# 4_Connectors.net
KiCad netlist of a schematic drawn in Altium Designer
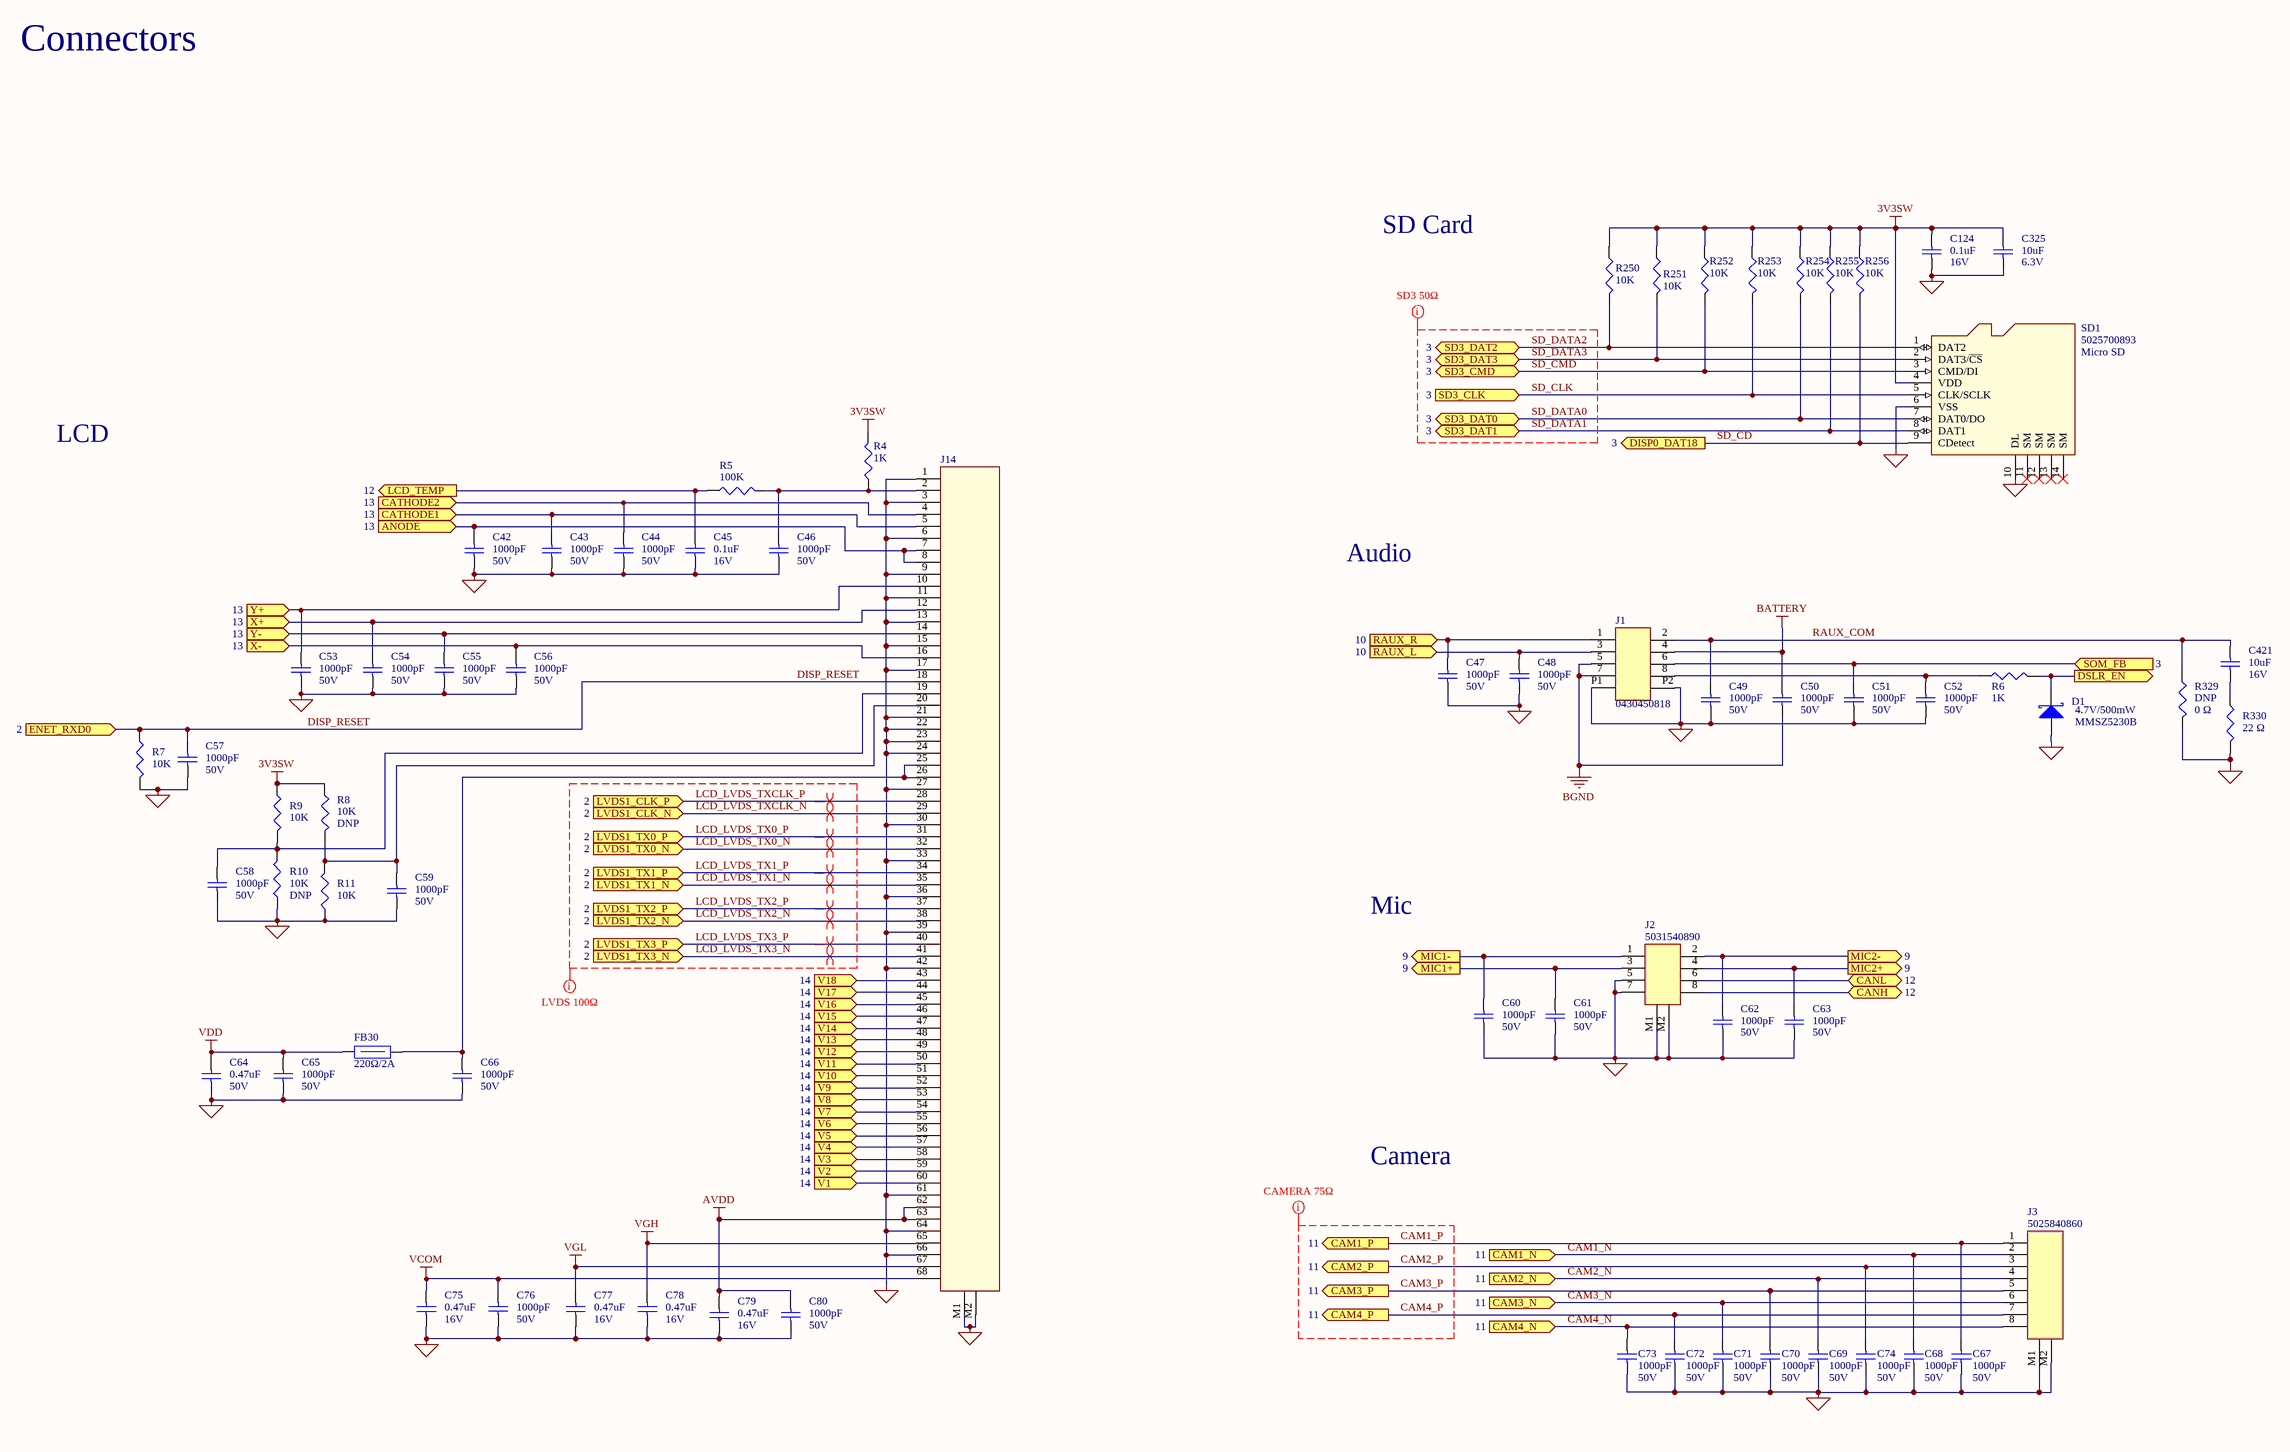
[diagram p0: 4 Connectors.SchDoc]

(export (version "E")
  (design (tool "Eeschema 10.0.6"))
  (components
    (comp (ref "C42")
      (value "1000pF")
      (footprint "CAP_0402")
      (description "Cap, Cer, 1000pF, 50V, 20%, X7R, 0402")
      (fields
        (field (name "TOLERANCE") "20%")
        (field (name "MANUFACTURER") "Murata Electronics North America")
        (field (name "VOLTAGE") "50V")
      )
      (libsource (lib "Firstview") (part "Cap 1000pF 50V 0402"))
    )
    (comp (ref "C43")
      (value "1000pF")
      (footprint "CAP_0402")
      (description "Cap, Cer, 1000pF, 50V, 20%, X7R, 0402")
      (fields
        (field (name "TOLERANCE") "20%")
        (field (name "MANUFACTURER") "Murata Electronics North America")
        (field (name "VOLTAGE") "50V")
      )
      (libsource (lib "Firstview") (part "Cap 1000pF 50V 0402"))
    )
    (comp (ref "C44")
      (value "1000pF")
      (footprint "CAP_0402")
      (description "Cap, Cer, 1000pF, 50V, 20%, X7R, 0402")
      (fields
        (field (name "TOLERANCE") "20%")
        (field (name "MANUFACTURER") "Murata Electronics North America")
        (field (name "VOLTAGE") "50V")
      )
      (libsource (lib "Firstview") (part "Cap 1000pF 50V 0402"))
    )
    (comp (ref "C45")
      (value "0.1uF")
      (footprint "CAP_0402")
      (description "Cap, Cer, 0.1uF, 16V, 10%, X7R, 0402")
      (fields
        (field (name "TOLERANCE") "±10%")
        (field (name "MANUFACTURER") "Murata Electronics North America")
        (field (name "VOLTAGE") "16V")
      )
      (libsource (lib "Firstview") (part "Cap 0.1uF 16V 0402"))
    )
    (comp (ref "C46")
      (value "1000pF")
      (footprint "CAP_0402")
      (description "Cap, Cer, 1000pF, 50V, 20%, X7R, 0402")
      (fields
        (field (name "TOLERANCE") "20%")
        (field (name "MANUFACTURER") "Murata Electronics North America")
        (field (name "VOLTAGE") "50V")
      )
      (libsource (lib "Firstview") (part "Cap 1000pF 50V 0402"))
    )
    (comp (ref "C47")
      (value "1000pF")
      (footprint "CAP_0402")
      (description "Cap, Cer, 1000pF, 50V, 20%, X7R, 0402")
      (fields
        (field (name "TOLERANCE") "20%")
        (field (name "MANUFACTURER") "Murata Electronics North America")
        (field (name "VOLTAGE") "50V")
      )
      (libsource (lib "Firstview") (part "Cap 1000pF 50V 0402"))
    )
    (comp (ref "C48")
      (value "1000pF")
      (footprint "CAP_0402")
      (description "Cap, Cer, 1000pF, 50V, 20%, X7R, 0402")
      (fields
        (field (name "TOLERANCE") "20%")
        (field (name "MANUFACTURER") "Murata Electronics North America")
        (field (name "VOLTAGE") "50V")
      )
      (libsource (lib "Firstview") (part "Cap 1000pF 50V 0402"))
    )
    (comp (ref "C49")
      (value "1000pF")
      (footprint "CAP_0402")
      (description "Cap, Cer, 1000pF, 50V, 20%, X7R, 0402")
      (fields
        (field (name "TOLERANCE") "20%")
        (field (name "MANUFACTURER") "Murata Electronics North America")
        (field (name "VOLTAGE") "50V")
      )
      (libsource (lib "Firstview") (part "Cap 1000pF 50V 0402"))
    )
    (comp (ref "C50")
      (value "1000pF")
      (footprint "CAP_0402")
      (description "Cap, Cer, 1000pF, 50V, 20%, X7R, 0402")
      (fields
        (field (name "TOLERANCE") "20%")
        (field (name "MANUFACTURER") "Murata Electronics North America")
        (field (name "VOLTAGE") "50V")
      )
      (libsource (lib "Firstview") (part "Cap 1000pF 50V 0402"))
    )
    (comp (ref "C51")
      (value "1000pF")
      (footprint "CAP_0402")
      (description "Cap, Cer, 1000pF, 50V, 20%, X7R, 0402")
      (fields
        (field (name "TOLERANCE") "20%")
        (field (name "MANUFACTURER") "Murata Electronics North America")
        (field (name "VOLTAGE") "50V")
      )
      (libsource (lib "Firstview") (part "Cap 1000pF 50V 0402"))
    )
    (comp (ref "C52")
      (value "1000pF")
      (footprint "CAP_0402")
      (description "Cap, Cer, 1000pF, 50V, 20%, X7R, 0402")
      (fields
        (field (name "TOLERANCE") "20%")
        (field (name "MANUFACTURER") "Murata Electronics North America")
        (field (name "VOLTAGE") "50V")
      )
      (libsource (lib "Firstview") (part "Cap 1000pF 50V 0402"))
    )
    (comp (ref "C53")
      (value "1000pF")
      (footprint "CAP_0402")
      (description "Cap, Cer, 1000pF, 50V, 20%, X7R, 0402")
      (fields
        (field (name "TOLERANCE") "20%")
        (field (name "MANUFACTURER") "Murata Electronics North America")
        (field (name "VOLTAGE") "50V")
      )
      (libsource (lib "Firstview") (part "Cap 1000pF 50V 0402"))
    )
    (comp (ref "C54")
      (value "1000pF")
      (footprint "CAP_0402")
      (description "Cap, Cer, 1000pF, 50V, 20%, X7R, 0402")
      (fields
        (field (name "TOLERANCE") "20%")
        (field (name "MANUFACTURER") "Murata Electronics North America")
        (field (name "VOLTAGE") "50V")
      )
      (libsource (lib "Firstview") (part "Cap 1000pF 50V 0402"))
    )
    (comp (ref "C55")
      (value "1000pF")
      (footprint "CAP_0402")
      (description "Cap, Cer, 1000pF, 50V, 20%, X7R, 0402")
      (fields
        (field (name "TOLERANCE") "20%")
        (field (name "MANUFACTURER") "Murata Electronics North America")
        (field (name "VOLTAGE") "50V")
      )
      (libsource (lib "Firstview") (part "Cap 1000pF 50V 0402"))
    )
    (comp (ref "C56")
      (value "1000pF")
      (footprint "CAP_0402")
      (description "Cap, Cer, 1000pF, 50V, 20%, X7R, 0402")
      (fields
        (field (name "TOLERANCE") "20%")
        (field (name "MANUFACTURER") "Murata Electronics North America")
        (field (name "VOLTAGE") "50V")
      )
      (libsource (lib "Firstview") (part "Cap 1000pF 50V 0402"))
    )
    (comp (ref "C57")
      (value "1000pF")
      (footprint "CAP_0402")
      (description "Cap, Cer, 1000pF, 50V, 20%, X7R, 0402")
      (fields
        (field (name "TOLERANCE") "20%")
        (field (name "MANUFACTURER") "Murata Electronics North America")
        (field (name "VOLTAGE") "50V")
      )
      (libsource (lib "Firstview") (part "Cap 1000pF 50V 0402"))
    )
    (comp (ref "C58")
      (value "1000pF")
      (footprint "CAP_0402")
      (description "Cap, Cer, 1000pF, 50V, 20%, X7R, 0402")
      (fields
        (field (name "TOLERANCE") "20%")
        (field (name "MANUFACTURER") "Murata Electronics North America")
        (field (name "VOLTAGE") "50V")
      )
      (libsource (lib "Firstview") (part "Cap 1000pF 50V 0402"))
    )
    (comp (ref "C59")
      (value "1000pF")
      (footprint "CAP_0402")
      (description "Cap, Cer, 1000pF, 50V, 20%, X7R, 0402")
      (fields
        (field (name "TOLERANCE") "20%")
        (field (name "MANUFACTURER") "Murata Electronics North America")
        (field (name "VOLTAGE") "50V")
      )
      (libsource (lib "Firstview") (part "Cap 1000pF 50V 0402"))
    )
    (comp (ref "C60")
      (value "1000pF")
      (footprint "CAP_0402")
      (description "Cap, Cer, 1000pF, 50V, 20%, X7R, 0402")
      (fields
        (field (name "TOLERANCE") "20%")
        (field (name "MANUFACTURER") "Murata Electronics North America")
        (field (name "VOLTAGE") "50V")
      )
      (libsource (lib "Firstview") (part "Cap 1000pF 50V 0402"))
    )
    (comp (ref "C61")
      (value "1000pF")
      (footprint "CAP_0402")
      (description "Cap, Cer, 1000pF, 50V, 20%, X7R, 0402")
      (fields
        (field (name "TOLERANCE") "20%")
        (field (name "MANUFACTURER") "Murata Electronics North America")
        (field (name "VOLTAGE") "50V")
      )
      (libsource (lib "Firstview") (part "Cap 1000pF 50V 0402"))
    )
    (comp (ref "C62")
      (value "1000pF")
      (footprint "CAP_0402")
      (description "Cap, Cer, 1000pF, 50V, 20%, X7R, 0402")
      (fields
        (field (name "TOLERANCE") "20%")
        (field (name "MANUFACTURER") "Murata Electronics North America")
        (field (name "VOLTAGE") "50V")
      )
      (libsource (lib "Firstview") (part "Cap 1000pF 50V 0402"))
    )
    (comp (ref "C63")
      (value "1000pF")
      (footprint "CAP_0402")
      (description "Cap, Cer, 1000pF, 50V, 20%, X7R, 0402")
      (fields
        (field (name "TOLERANCE") "20%")
        (field (name "MANUFACTURER") "Murata Electronics North America")
        (field (name "VOLTAGE") "50V")
      )
      (libsource (lib "Firstview") (part "Cap 1000pF 50V 0402"))
    )
    (comp (ref "C64")
      (value "0.47uF")
      (footprint "CAP_1206")
      (description "Cap, Cer, 0.47uF, 50V, 10%, X7R, 1206")
      (fields
        (field (name "MANUFACTURER") "Yageo")
        (field (name "TOLERANCE") "10%")
        (field (name "VOLTAGE") "50V")
      )
      (libsource (lib "Firstview") (part "Cap 0.47uF 50V 1206"))
    )
    (comp (ref "C65")
      (value "1000pF")
      (footprint "CAP_0402")
      (description "Cap, Cer, 1000pF, 50V, 20%, X7R, 0402")
      (fields
        (field (name "TOLERANCE") "20%")
        (field (name "MANUFACTURER") "Murata Electronics North America")
        (field (name "VOLTAGE") "50V")
      )
      (libsource (lib "Firstview") (part "Cap 1000pF 50V 0402"))
    )
    (comp (ref "C66")
      (value "1000pF")
      (footprint "CAP_0402")
      (description "Cap, Cer, 1000pF, 50V, 20%, X7R, 0402")
      (fields
        (field (name "TOLERANCE") "20%")
        (field (name "MANUFACTURER") "Murata Electronics North America")
        (field (name "VOLTAGE") "50V")
      )
      (libsource (lib "Firstview") (part "Cap 1000pF 50V 0402"))
    )
    (comp (ref "C67")
      (value "1000pF")
      (footprint "CAP_0402")
      (description "Cap, Cer, 1000pF, 50V, 20%, X7R, 0402")
      (fields
        (field (name "TOLERANCE") "20%")
        (field (name "MANUFACTURER") "Murata Electronics North America")
        (field (name "VOLTAGE") "50V")
      )
      (libsource (lib "Firstview") (part "Cap 1000pF 50V 0402"))
    )
    (comp (ref "C68")
      (value "1000pF")
      (footprint "CAP_0402")
      (description "Cap, Cer, 1000pF, 50V, 20%, X7R, 0402")
      (fields
        (field (name "TOLERANCE") "20%")
        (field (name "MANUFACTURER") "Murata Electronics North America")
        (field (name "VOLTAGE") "50V")
      )
      (libsource (lib "Firstview") (part "Cap 1000pF 50V 0402"))
    )
    (comp (ref "C69")
      (value "1000pF")
      (footprint "CAP_0402")
      (description "Cap, Cer, 1000pF, 50V, 20%, X7R, 0402")
      (fields
        (field (name "TOLERANCE") "20%")
        (field (name "MANUFACTURER") "Murata Electronics North America")
        (field (name "VOLTAGE") "50V")
      )
      (libsource (lib "Firstview") (part "Cap 1000pF 50V 0402"))
    )
    (comp (ref "C70")
      (value "1000pF")
      (footprint "CAP_0402")
      (description "Cap, Cer, 1000pF, 50V, 20%, X7R, 0402")
      (fields
        (field (name "TOLERANCE") "20%")
        (field (name "MANUFACTURER") "Murata Electronics North America")
        (field (name "VOLTAGE") "50V")
      )
      (libsource (lib "Firstview") (part "Cap 1000pF 50V 0402"))
    )
    (comp (ref "C71")
      (value "1000pF")
      (footprint "CAP_0402")
      (description "Cap, Cer, 1000pF, 50V, 20%, X7R, 0402")
      (fields
        (field (name "TOLERANCE") "20%")
        (field (name "MANUFACTURER") "Murata Electronics North America")
        (field (name "VOLTAGE") "50V")
      )
      (libsource (lib "Firstview") (part "Cap 1000pF 50V 0402"))
    )
    (comp (ref "C72")
      (value "1000pF")
      (footprint "CAP_0402")
      (description "Cap, Cer, 1000pF, 50V, 20%, X7R, 0402")
      (fields
        (field (name "TOLERANCE") "20%")
        (field (name "MANUFACTURER") "Murata Electronics North America")
        (field (name "VOLTAGE") "50V")
      )
      (libsource (lib "Firstview") (part "Cap 1000pF 50V 0402"))
    )
    (comp (ref "C73")
      (value "1000pF")
      (footprint "CAP_0402")
      (description "Cap, Cer, 1000pF, 50V, 20%, X7R, 0402")
      (fields
        (field (name "TOLERANCE") "20%")
        (field (name "MANUFACTURER") "Murata Electronics North America")
        (field (name "VOLTAGE") "50V")
      )
      (libsource (lib "Firstview") (part "Cap 1000pF 50V 0402"))
    )
    (comp (ref "C74")
      (value "1000pF")
      (footprint "CAP_0402")
      (description "Cap, Cer, 1000pF, 50V, 20%, X7R, 0402")
      (fields
        (field (name "TOLERANCE") "20%")
        (field (name "MANUFACTURER") "Murata Electronics North America")
        (field (name "VOLTAGE") "50V")
      )
      (libsource (lib "Firstview") (part "Cap 1000pF 50V 0402"))
    )
    (comp (ref "C75")
      (value "0.47uF")
      (footprint "CAP_0603")
      (description "Cap, Cer, 0.47uF, 16V, 10%, X8R, 0603")
      (fields
        (field (name "MANUFACTURER") "TDK Corporation")
        (field (name "TOLERANCE") "10%")
        (field (name "VOLTAGE") "16V")
      )
      (libsource (lib "Firstview") (part "Cap 0.47uF 16V 0603"))
    )
    (comp (ref "C76")
      (value "1000pF")
      (footprint "CAP_0402")
      (description "Cap, Cer, 1000pF, 50V, 20%, X7R, 0402")
      (fields
        (field (name "TOLERANCE") "20%")
        (field (name "MANUFACTURER") "Murata Electronics North America")
        (field (name "VOLTAGE") "50V")
      )
      (libsource (lib "Firstview") (part "Cap 1000pF 50V 0402"))
    )
    (comp (ref "C77")
      (value "0.47uF")
      (footprint "CAP_0603")
      (description "Cap, Cer, 0.47uF, 16V, 10%, X8R, 0603")
      (fields
        (field (name "MANUFACTURER") "TDK Corporation")
        (field (name "TOLERANCE") "10%")
        (field (name "VOLTAGE") "16V")
      )
      (libsource (lib "Firstview") (part "Cap 0.47uF 16V 0603"))
    )
    (comp (ref "C78")
      (value "0.47uF")
      (footprint "CAP_0603")
      (description "Cap, Cer, 0.47uF, 16V, 10%, X8R, 0603")
      (fields
        (field (name "MANUFACTURER") "TDK Corporation")
        (field (name "TOLERANCE") "10%")
        (field (name "VOLTAGE") "16V")
      )
      (libsource (lib "Firstview") (part "Cap 0.47uF 16V 0603"))
    )
    (comp (ref "C79")
      (value "0.47uF")
      (footprint "CAP_0603")
      (description "Cap, Cer, 0.47uF, 16V, 10%, X8R, 0603")
      (fields
        (field (name "MANUFACTURER") "TDK Corporation")
        (field (name "TOLERANCE") "10%")
        (field (name "VOLTAGE") "16V")
      )
      (libsource (lib "Firstview") (part "Cap 0.47uF 16V 0603"))
    )
    (comp (ref "C80")
      (value "1000pF")
      (footprint "CAP_0402")
      (description "Cap, Cer, 1000pF, 50V, 20%, X7R, 0402")
      (fields
        (field (name "TOLERANCE") "20%")
        (field (name "MANUFACTURER") "Murata Electronics North America")
        (field (name "VOLTAGE") "50V")
      )
      (libsource (lib "Firstview") (part "Cap 1000pF 50V 0402"))
    )
    (comp (ref "C124")
      (value "0.1uF")
      (footprint "CAP_0402")
      (description "Cap, Cer, 0.1uF, 16V, 10%, X7R, 0402")
      (fields
        (field (name "TOLERANCE") "±10%")
        (field (name "MANUFACTURER") "Murata Electronics North America")
        (field (name "VOLTAGE") "16V")
      )
      (libsource (lib "Firstview") (part "Cap 0.1uF 16V 0402"))
    )
    (comp (ref "C325")
      (value "10uF")
      (footprint "CAP_0402")
      (description "Cap, Cer, 10uF, 6.3V, 20%, X5R, 0402")
      (fields
        (field (name "TOLERANCE") "±20%")
        (field (name "MANUFACTURER") "Samsung Electro-Mechanics America, Inc")
        (field (name "VOLTAGE") "6.3V")
      )
      (libsource (lib "Firstview") (part "Cap 10uF 6.3V 0402"))
    )
    (comp (ref "C421")
      (value "10uF")
      (footprint "CAP_0603")
      (description "Cap, Cer, 10uF, 16V, 20%, X5R, 0603")
      (fields
        (field (name "TOLERANCE") "±20%")
        (field (name "MANUFACTURER") "Murata Electronics North America")
        (field (name "VOLTAGE") "16V")
      )
      (libsource (lib "Firstview") (part "Cap 10uF 16V 0603"))
    )
    (comp (ref "D1")
      (value "MMSZ5230B")
      (footprint "SOD-123_MMSZ5230B")
      (description "Diode, Zener, 4.7V, 500mW, SOD-123")
      (fields (field (name "MANUFACTURER") "Diodes Incorporated") (field (name "ALTIUM_VALUE") "4.7V/500mW"))
      (libsource (lib "Firstview") (part "MMSZ5230B"))
    )
    (comp (ref "FB30")
      (value "220Ω/2A")
      (footprint "IND_0805")
      (description "Ind, Ferrite Bead, 220R, 50mOhm, 2A, 0805")
      (fields (field (name "MANUFACTURER") "Taiyo Yuden") (field (name "Comment") "BKP2125HS221-T"))
      (libsource (lib "Firstview") (part "BKP2125HS221-T"))
    )
    (comp (ref "J1")
      (value "0430450818")
      (footprint "CON_0430450818")
      (description "Conn, Header, 8 pos, 3mm pitch, SMD")
      (fields (field (name "MANUFACTURER") "Molex Inc"))
      (libsource (lib "Firstview") (part "0430450818"))
    )
    (comp (ref "J2")
      (value "5031540890")
      (footprint "CON_5031540890")
      (description "Conn, Receptacle, 8 pos, 1.5mm pitch, SMD")
      (fields (field (name "MANUFACTURER") "Molex Inc"))
      (libsource (lib "Firstview") (part "5031540890"))
    )
    (comp (ref "J3")
      (value "5025840860")
      (footprint "CON_5025840860")
      (description "Conn, Receptacle, 8 pos, 1.5mm pitch, SMD")
      (fields (field (name "MANUFACTURER") "Molex Inc"))
      (libsource (lib "Firstview") (part "5025840860"))
    )
    (comp (ref "J14")
      (value "FH28E-68S-0.5SH(05)")
      (footprint "CON_FH28E-68S-0.5SH(05)")
      (description "Conn, FPC/FFC, 68Pos, .5MM, Horz., SMD")
      (fields (field (name "MANUFACTURER") "Hirose Electric Co Ltd"))
      (libsource (lib "Firstview") (part "FH28E-68S-0.5SH(05)"))
    )
    (comp (ref "R4")
      (value "1K")
      (footprint "RES_0402")
      (description "Res, 1K, 0.063W, 1%, 0402")
      (fields (field (name "TOLERANCE") "±1%") (field (name "MANUFACTURER") "Vishay Dale"))
      (libsource (lib "Firstview") (part "Res 1K 0.063W"))
    )
    (comp (ref "R5")
      (value "100K")
      (footprint "RES_0402")
      (description "Res, 100K, 0.1W, 1%, 0402")
      (fields
        (field (name "MANUFACTURER") "Panasonic Electronic Components")
        (field (name "Comment") "Res 100K 0.1W")
      )
      (libsource (lib "Firstview") (part "Res 100K 0.1W"))
    )
    (comp (ref "R6")
      (value "1K")
      (footprint "RES_0402")
      (description "Res, 1K, 0.063W, 1%, 0402")
      (fields (field (name "TOLERANCE") "±1%") (field (name "MANUFACTURER") "Vishay Dale"))
      (libsource (lib "Firstview") (part "Res 1K 0.063W"))
    )
    (comp (ref "R7")
      (value "10K")
      (footprint "RES_0402")
      (description "Res, 10K, 1/16W, 1%, 0402")
      (fields (field (name "MANUFACTURER") "Yageo") (field (name "Comment") "Res 10K 0.063W"))
      (libsource (lib "Firstview") (part "Res 10K 0.063W"))
    )
    (comp (ref "R8")
      (value "10K")
      (footprint "RES_0402")
      (description "Res, 10K, 1/16W, 1%, 0402")
      (fields
        (field (name "DNP") "DNP")
        (field (name "MANUFACTURER") "Yageo")
        (field (name "Comment") "Res 10K 0.063W")
      )
      (libsource (lib "Firstview") (part "Res 10K 0.063W"))
    )
    (comp (ref "R9")
      (value "10K")
      (footprint "RES_0402")
      (description "Res, 10K, 1/16W, 1%, 0402")
      (fields (field (name "MANUFACTURER") "Yageo") (field (name "Comment") "Res 10K 0.063W"))
      (libsource (lib "Firstview") (part "Res 10K 0.063W"))
    )
    (comp (ref "R10")
      (value "10K")
      (footprint "RES_0402")
      (description "Res, 10K, 1/16W, 1%, 0402")
      (fields
        (field (name "DNP") "DNP")
        (field (name "MANUFACTURER") "Yageo")
        (field (name "Comment") "Res 10K 0.063W")
      )
      (libsource (lib "Firstview") (part "Res 10K 0.063W"))
    )
    (comp (ref "R11")
      (value "10K")
      (footprint "RES_0402")
      (description "Res, 10K, 1/16W, 1%, 0402")
      (fields (field (name "MANUFACTURER") "Yageo") (field (name "Comment") "Res 10K 0.063W"))
      (libsource (lib "Firstview") (part "Res 10K 0.063W"))
    )
    (comp (ref "R250")
      (value "10K")
      (footprint "RES_0402")
      (description "Res, 10K, 1/16W, 1%, 0402")
      (fields (field (name "MANUFACTURER") "Yageo") (field (name "Comment") "Res 10K 0.063W"))
      (libsource (lib "Firstview") (part "Res 10K 0.063W"))
    )
    (comp (ref "R251")
      (value "10K")
      (footprint "RES_0402")
      (description "Res, 10K, 1/16W, 1%, 0402")
      (fields (field (name "MANUFACTURER") "Yageo") (field (name "Comment") "Res 10K 0.063W"))
      (libsource (lib "Firstview") (part "Res 10K 0.063W"))
    )
    (comp (ref "R252")
      (value "10K")
      (footprint "RES_0402")
      (description "Res, 10K, 1/16W, 1%, 0402")
      (fields (field (name "MANUFACTURER") "Yageo") (field (name "Comment") "Res 10K 0.063W"))
      (libsource (lib "Firstview") (part "Res 10K 0.063W"))
    )
    (comp (ref "R253")
      (value "10K")
      (footprint "RES_0402")
      (description "Res, 10K, 1/16W, 1%, 0402")
      (fields (field (name "MANUFACTURER") "Yageo") (field (name "Comment") "Res 10K 0.063W"))
      (libsource (lib "Firstview") (part "Res 10K 0.063W"))
    )
    (comp (ref "R254")
      (value "10K")
      (footprint "RES_0402")
      (description "Res, 10K, 1/16W, 1%, 0402")
      (fields (field (name "MANUFACTURER") "Yageo") (field (name "Comment") "Res 10K 0.063W"))
      (libsource (lib "Firstview") (part "Res 10K 0.063W"))
    )
    (comp (ref "R255")
      (value "10K")
      (footprint "RES_0402")
      (description "Res, 10K, 1/16W, 1%, 0402")
      (fields (field (name "MANUFACTURER") "Yageo") (field (name "Comment") "Res 10K 0.063W"))
      (libsource (lib "Firstview") (part "Res 10K 0.063W"))
    )
    (comp (ref "R256")
      (value "10K")
      (footprint "RES_0402")
      (description "Res, 10K, 1/16W, 1%, 0402")
      (fields (field (name "MANUFACTURER") "Yageo") (field (name "Comment") "Res 10K 0.063W"))
      (libsource (lib "Firstview") (part "Res 10K 0.063W"))
    )
    (comp (ref "R329")
      (value "0 Ω")
      (footprint "RES_0402")
      (description "Res, 0 ohm, 1/16W, 0402")
      (fields
        (field (name "MANUFACTURER") "Vishay Dale")
        (field (name "DNP") "DNP")
        (field (name "Comment") "Res 0 ohm 0.1W DNP")
      )
      (libsource (lib "Firstview") (part "Res 0 ohm 0.1W DNP"))
    )
    (comp (ref "R330")
      (value "22 Ω")
      (footprint "RES_0402")
      (description "Res, 22R, 0.063W, 1%, 0402")
      (fields (field (name "TOLERANCE") "±1%") (field (name "MANUFACTURER") "Yageo"))
      (libsource (lib "Firstview") (part "Res 22R 0.063W"))
    )
    (comp (ref "SD1")
      (value "5025700893")
      (footprint "SD_502570-0893")
      (description "Conn, Mico SD, RT, SMD")
      (fields (field (name "MANUFACTURER") "Molex Inc") (field (name "ALTIUM_VALUE") "Micro SD"))
      (libsource (lib "Firstview") (part "5025700893"))
    )
  )
  (nets
    (net (code "1") (name "/ANODE") (class "Default")
      (node (ref "C42") (pin "1") (pinfunction "1_1") (pintype "passive"))
      (node (ref "J14") (pin "7") (pinfunction "7_7") (pintype "passive"))
      (node (ref "J14") (pin "8") (pinfunction "8_8") (pintype "passive"))
    )
    (net (code "2") (name "/CAM1_N") (class "Default")
      (node (ref "C68") (pin "1") (pinfunction "1_1") (pintype "passive"))
      (node (ref "J3") (pin "2") (pinfunction "2_2") (pintype "passive"))
    )
    (net (code "3") (name "/CAM1_P") (class "Default")
      (node (ref "C67") (pin "1") (pinfunction "1_1") (pintype "passive"))
      (node (ref "J3") (pin "1") (pinfunction "1_1") (pintype "passive"))
    )
    (net (code "4") (name "/CAM2_N") (class "Default")
      (node (ref "C69") (pin "1") (pinfunction "1_1") (pintype "passive"))
      (node (ref "J3") (pin "4") (pinfunction "4_4") (pintype "passive"))
    )
    (net (code "5") (name "/CAM2_P") (class "Default")
      (node (ref "C74") (pin "1") (pinfunction "1_1") (pintype "passive"))
      (node (ref "J3") (pin "3") (pinfunction "3_3") (pintype "passive"))
    )
    (net (code "6") (name "/CAM3_N") (class "Default")
      (node (ref "C71") (pin "1") (pinfunction "1_1") (pintype "passive"))
      (node (ref "J3") (pin "6") (pinfunction "6_6") (pintype "passive"))
    )
    (net (code "7") (name "/CAM3_P") (class "Default")
      (node (ref "C70") (pin "1") (pinfunction "1_1") (pintype "passive"))
      (node (ref "J3") (pin "5") (pinfunction "5_5") (pintype "passive"))
    )
    (net (code "8") (name "/CAM4_N") (class "Default")
      (node (ref "C73") (pin "1") (pinfunction "1_1") (pintype "passive"))
      (node (ref "J3") (pin "8") (pinfunction "8_8") (pintype "passive"))
    )
    (net (code "9") (name "/CAM4_P") (class "Default")
      (node (ref "C72") (pin "1") (pinfunction "1_1") (pintype "passive"))
      (node (ref "J3") (pin "7") (pinfunction "7_7") (pintype "passive"))
    )
    (net (code "10") (name "/CANH") (class "Default")
      (node (ref "J2") (pin "8") (pinfunction "8_8") (pintype "passive"))
    )
    (net (code "11") (name "/CANL") (class "Default")
      (node (ref "J2") (pin "6") (pinfunction "6_6") (pintype "passive"))
    )
    (net (code "12") (name "/CATHODE1") (class "Default")
      (node (ref "C43") (pin "1") (pinfunction "1_1") (pintype "passive"))
      (node (ref "J14") (pin "5") (pinfunction "5_5") (pintype "passive"))
    )
    (net (code "13") (name "/CATHODE2") (class "Default")
      (node (ref "C44") (pin "1") (pinfunction "1_1") (pintype "passive"))
      (node (ref "J14") (pin "4") (pinfunction "4_4") (pintype "passive"))
    )
    (net (code "14") (name "/DISP_RESET") (class "Default")
      (node (ref "C57") (pin "1") (pinfunction "1_1") (pintype "passive"))
      (node (ref "J14") (pin "18") (pinfunction "18_18") (pintype "passive"))
      (node (ref "R7") (pin "1") (pinfunction "1_1") (pintype "passive"))
    )
    (net (code "15") (name "/DSLR_EN") (class "Default")
      (node (ref "D1") (pin "K") (pinfunction "K_K") (pintype "passive"))
      (node (ref "R6") (pin "2") (pinfunction "2_2") (pintype "passive"))
    )
    (net (code "16") (name "/LCD_LVDS_TX0_N") (class "Default")
      (node (ref "J14") (pin "32") (pinfunction "32_32") (pintype "passive"))
    )
    (net (code "17") (name "/LCD_LVDS_TX0_P") (class "Default")
      (node (ref "J14") (pin "31") (pinfunction "31_31") (pintype "passive"))
    )
    (net (code "18") (name "/LCD_LVDS_TX1_N") (class "Default")
      (node (ref "J14") (pin "35") (pinfunction "35_35") (pintype "passive"))
    )
    (net (code "19") (name "/LCD_LVDS_TX1_P") (class "Default")
      (node (ref "J14") (pin "34") (pinfunction "34_34") (pintype "passive"))
    )
    (net (code "20") (name "/LCD_LVDS_TX2_N") (class "Default")
      (node (ref "J14") (pin "38") (pinfunction "38_38") (pintype "passive"))
    )
    (net (code "21") (name "/LCD_LVDS_TX2_P") (class "Default")
      (node (ref "J14") (pin "37") (pinfunction "37_37") (pintype "passive"))
    )
    (net (code "22") (name "/LCD_LVDS_TX3_N") (class "Default")
      (node (ref "J14") (pin "41") (pinfunction "41_41") (pintype "passive"))
    )
    (net (code "23") (name "/LCD_LVDS_TX3_P") (class "Default")
      (node (ref "J14") (pin "40") (pinfunction "40_40") (pintype "passive"))
    )
    (net (code "24") (name "/LCD_LVDS_TXCLK_N") (class "Default")
      (node (ref "J14") (pin "29") (pinfunction "29_29") (pintype "passive"))
    )
    (net (code "25") (name "/LCD_LVDS_TXCLK_P") (class "Default")
      (node (ref "J14") (pin "28") (pinfunction "28_28") (pintype "passive"))
    )
    (net (code "26") (name "/LCD_TEMP") (class "Default")
      (node (ref "C45") (pin "1") (pinfunction "1_1") (pintype "passive"))
      (node (ref "R5") (pin "1") (pinfunction "1_1") (pintype "passive"))
    )
    (net (code "27") (name "/MIC1+") (class "Default")
      (node (ref "C61") (pin "1") (pinfunction "1_1") (pintype "passive"))
      (node (ref "J2") (pin "3") (pinfunction "3_3") (pintype "passive"))
    )
    (net (code "28") (name "/MIC1-") (class "Default")
      (node (ref "C60") (pin "1") (pinfunction "1_1") (pintype "passive"))
      (node (ref "J2") (pin "1") (pinfunction "1_1") (pintype "passive"))
    )
    (net (code "29") (name "/MIC2+") (class "Default")
      (node (ref "C63") (pin "1") (pinfunction "1_1") (pintype "passive"))
      (node (ref "J2") (pin "4") (pinfunction "4_4") (pintype "passive"))
    )
    (net (code "30") (name "/MIC2-") (class "Default")
      (node (ref "C62") (pin "1") (pinfunction "1_1") (pintype "passive"))
      (node (ref "J2") (pin "2") (pinfunction "2_2") (pintype "passive"))
    )
    (net (code "31") (name "/RAUX_COM") (class "Default")
      (node (ref "C421") (pin "1") (pinfunction "1_1") (pintype "passive"))
      (node (ref "C49") (pin "1") (pinfunction "1_1") (pintype "passive"))
      (node (ref "J1") (pin "2") (pinfunction "2_2") (pintype "passive"))
      (node (ref "R329") (pin "1") (pinfunction "1_1") (pintype "passive"))
    )
    (net (code "32") (name "/RAUX_L") (class "Default")
      (node (ref "C48") (pin "1") (pinfunction "1_1") (pintype "passive"))
      (node (ref "J1") (pin "3") (pinfunction "3_3") (pintype "passive"))
    )
    (net (code "33") (name "/RAUX_R") (class "Default")
      (node (ref "C47") (pin "1") (pinfunction "1_1") (pintype "passive"))
      (node (ref "J1") (pin "1") (pinfunction "1_1") (pintype "passive"))
    )
    (net (code "34") (name "/SD_CD") (class "Default")
      (node (ref "R256") (pin "2") (pinfunction "2_2") (pintype "passive"))
      (node (ref "SD1") (pin "9") (pinfunction "CDetect_9") (pintype "passive"))
    )
    (net (code "35") (name "/SD_CLK") (class "Default")
      (node (ref "R253") (pin "2") (pinfunction "2_2") (pintype "passive"))
      (node (ref "SD1") (pin "5") (pinfunction "CLK/SCLK_5") (pintype "input"))
    )
    (net (code "36") (name "/SD_CMD") (class "Default")
      (node (ref "R252") (pin "2") (pinfunction "2_2") (pintype "passive"))
      (node (ref "SD1") (pin "3") (pinfunction "CMD/DI_3") (pintype "input"))
    )
    (net (code "37") (name "/SD_DATA0") (class "Default")
      (node (ref "R254") (pin "2") (pinfunction "2_2") (pintype "passive"))
      (node (ref "SD1") (pin "7") (pinfunction "DAT0/DO_7") (pintype "bidirectional"))
    )
    (net (code "38") (name "/SD_DATA1") (class "Default")
      (node (ref "R255") (pin "2") (pinfunction "2_2") (pintype "passive"))
      (node (ref "SD1") (pin "8") (pinfunction "DAT1_8") (pintype "bidirectional"))
    )
    (net (code "39") (name "/SD_DATA2") (class "Default")
      (node (ref "R250") (pin "2") (pinfunction "2_2") (pintype "passive"))
      (node (ref "SD1") (pin "1") (pinfunction "DAT2_1") (pintype "bidirectional"))
    )
    (net (code "40") (name "/SD_DATA3") (class "Default")
      (node (ref "R251") (pin "2") (pinfunction "2_2") (pintype "passive"))
      (node (ref "SD1") (pin "2") (pinfunction "DAT3/~{CS}_2") (pintype "input"))
    )
    (net (code "41") (name "/SOM_FB") (class "Default")
      (node (ref "C51") (pin "1") (pinfunction "1_1") (pintype "passive"))
      (node (ref "J1") (pin "6") (pinfunction "6_6") (pintype "passive"))
    )
    (net (code "42") (name "/V1") (class "Default") (node (ref "J14") (pin "60") (pintype "passive")))
    (net (code "43") (name "/V2") (class "Default") (node (ref "J14") (pin "59") (pintype "passive")))
    (net (code "44") (name "/V3") (class "Default") (node (ref "J14") (pin "58") (pintype "passive")))
    (net (code "45") (name "/V4") (class "Default") (node (ref "J14") (pin "57") (pintype "passive")))
    (net (code "46") (name "/V5") (class "Default") (node (ref "J14") (pin "56") (pintype "passive")))
    (net (code "47") (name "/V6") (class "Default") (node (ref "J14") (pin "55") (pintype "passive")))
    (net (code "48") (name "/V7") (class "Default") (node (ref "J14") (pin "54") (pintype "passive")))
    (net (code "49") (name "/V8") (class "Default") (node (ref "J14") (pin "53") (pintype "passive")))
    (net (code "50") (name "/V9") (class "Default") (node (ref "J14") (pin "52") (pintype "passive")))
    (net (code "51") (name "/V10") (class "Default")
      (node (ref "J14") (pin "51") (pinfunction "51_51") (pintype "passive"))
    )
    (net (code "52") (name "/V11") (class "Default")
      (node (ref "J14") (pin "50") (pinfunction "50_50") (pintype "passive"))
    )
    (net (code "53") (name "/V12") (class "Default")
      (node (ref "J14") (pin "49") (pinfunction "49_49") (pintype "passive"))
    )
    (net (code "54") (name "/V13") (class "Default")
      (node (ref "J14") (pin "48") (pinfunction "48_48") (pintype "passive"))
    )
    (net (code "55") (name "/V14") (class "Default")
      (node (ref "J14") (pin "47") (pinfunction "47_47") (pintype "passive"))
    )
    (net (code "56") (name "/V15") (class "Default")
      (node (ref "J14") (pin "46") (pinfunction "46_46") (pintype "passive"))
    )
    (net (code "57") (name "/V16") (class "Default")
      (node (ref "J14") (pin "45") (pinfunction "45_45") (pintype "passive"))
    )
    (net (code "58") (name "/V17") (class "Default")
      (node (ref "J14") (pin "44") (pinfunction "44_44") (pintype "passive"))
    )
    (net (code "59") (name "/V18") (class "Default")
      (node (ref "J14") (pin "43") (pinfunction "43_43") (pintype "passive"))
    )
    (net (code "60") (name "/X+") (class "Default")
      (node (ref "C54") (pin "1") (pinfunction "1_1") (pintype "passive"))
      (node (ref "J14") (pin "12") (pinfunction "12_12") (pintype "passive"))
    )
    (net (code "61") (name "/X-") (class "Default")
      (node (ref "C56") (pin "1") (pinfunction "1_1") (pintype "passive"))
      (node (ref "J14") (pin "16") (pinfunction "16_16") (pintype "passive"))
    )
    (net (code "62") (name "/Y+") (class "Default")
      (node (ref "C53") (pin "1") (pinfunction "1_1") (pintype "passive"))
      (node (ref "J14") (pin "10") (pinfunction "10_10") (pintype "passive"))
    )
    (net (code "63") (name "/Y-") (class "Default")
      (node (ref "C55") (pin "1") (pinfunction "1_1") (pintype "passive"))
      (node (ref "J14") (pin "14") (pinfunction "14_14") (pintype "passive"))
    )
    (net (code "64") (name "3V3SW") (class "Default")
      (node (ref "C124") (pin "1") (pinfunction "1_1") (pintype "passive"))
      (node (ref "C325") (pin "1") (pinfunction "1_1") (pintype "passive"))
      (node (ref "R250") (pin "1") (pinfunction "1_1") (pintype "passive"))
      (node (ref "R251") (pin "1") (pinfunction "1_1") (pintype "passive"))
      (node (ref "R252") (pin "1") (pinfunction "1_1") (pintype "passive"))
      (node (ref "R253") (pin "1") (pinfunction "1_1") (pintype "passive"))
      (node (ref "R254") (pin "1") (pinfunction "1_1") (pintype "passive"))
      (node (ref "R255") (pin "1") (pinfunction "1_1") (pintype "passive"))
      (node (ref "R256") (pin "1") (pinfunction "1_1") (pintype "passive"))
      (node (ref "R4") (pin "2") (pinfunction "2_2") (pintype "passive"))
      (node (ref "R8") (pin "1") (pinfunction "1_1") (pintype "passive"))
      (node (ref "R9") (pin "1") (pinfunction "1_1") (pintype "passive"))
      (node (ref "SD1") (pin "4") (pinfunction "VDD_4") (pintype "power_in"))
    )
    (net (code "65") (name "AVDD") (class "Default")
      (node (ref "C79") (pin "1") (pinfunction "1_1") (pintype "passive"))
      (node (ref "C80") (pin "1") (pinfunction "1_1") (pintype "passive"))
      (node (ref "J14") (pin "62") (pintype "passive"))
      (node (ref "J14") (pin "63") (pintype "passive"))
    )
    (net (code "66") (name "BATTERY") (class "Default")
      (node (ref "C50") (pin "1") (pinfunction "1_1") (pintype "passive"))
      (node (ref "J1") (pin "4") (pinfunction "4_4") (pintype "passive"))
    )
    (net (code "67") (name "BGND") (class "Default")
      (node (ref "C50") (pin "2") (pinfunction "2_2") (pintype "passive"))
      (node (ref "J1") (pin "5") (pinfunction "5_5") (pintype "passive"))
      (node (ref "J1") (pin "7") (pinfunction "7_7") (pintype "passive"))
    )
    (net (code "68") (name "GND") (class "Default")
      (node (ref "C124") (pin "2") (pinfunction "2_2") (pintype "passive"))
      (node (ref "C325") (pin "2") (pinfunction "2_2") (pintype "passive"))
      (node (ref "C42") (pin "2") (pinfunction "2_2") (pintype "passive"))
      (node (ref "C43") (pin "2") (pinfunction "2_2") (pintype "passive"))
      (node (ref "C44") (pin "2") (pinfunction "2_2") (pintype "passive"))
      (node (ref "C45") (pin "2") (pinfunction "2_2") (pintype "passive"))
      (node (ref "C46") (pin "2") (pinfunction "2_2") (pintype "passive"))
      (node (ref "C47") (pin "2") (pinfunction "2_2") (pintype "passive"))
      (node (ref "C48") (pin "2") (pinfunction "2_2") (pintype "passive"))
      (node (ref "C49") (pin "2") (pinfunction "2_2") (pintype "passive"))
      (node (ref "C51") (pin "2") (pinfunction "2_2") (pintype "passive"))
      (node (ref "C52") (pin "2") (pinfunction "2_2") (pintype "passive"))
      (node (ref "C53") (pin "2") (pinfunction "2_2") (pintype "passive"))
      (node (ref "C54") (pin "2") (pinfunction "2_2") (pintype "passive"))
      (node (ref "C55") (pin "2") (pinfunction "2_2") (pintype "passive"))
      (node (ref "C56") (pin "2") (pinfunction "2_2") (pintype "passive"))
      (node (ref "C57") (pin "2") (pinfunction "2_2") (pintype "passive"))
      (node (ref "C58") (pin "2") (pinfunction "2_2") (pintype "passive"))
      (node (ref "C59") (pin "2") (pinfunction "2_2") (pintype "passive"))
      (node (ref "C60") (pin "2") (pinfunction "2_2") (pintype "passive"))
      (node (ref "C61") (pin "2") (pinfunction "2_2") (pintype "passive"))
      (node (ref "C62") (pin "2") (pinfunction "2_2") (pintype "passive"))
      (node (ref "C63") (pin "2") (pinfunction "2_2") (pintype "passive"))
      (node (ref "C64") (pin "2") (pinfunction "2_2") (pintype "passive"))
      (node (ref "C65") (pin "2") (pinfunction "2_2") (pintype "passive"))
      (node (ref "C66") (pin "2") (pinfunction "2_2") (pintype "passive"))
      (node (ref "C67") (pin "2") (pinfunction "2_2") (pintype "passive"))
      (node (ref "C68") (pin "2") (pinfunction "2_2") (pintype "passive"))
      (node (ref "C69") (pin "2") (pinfunction "2_2") (pintype "passive"))
      (node (ref "C70") (pin "2") (pinfunction "2_2") (pintype "passive"))
      (node (ref "C71") (pin "2") (pinfunction "2_2") (pintype "passive"))
      (node (ref "C72") (pin "2") (pinfunction "2_2") (pintype "passive"))
      (node (ref "C73") (pin "2") (pinfunction "2_2") (pintype "passive"))
      (node (ref "C74") (pin "2") (pinfunction "2_2") (pintype "passive"))
      (node (ref "C75") (pin "2") (pinfunction "2_2") (pintype "passive"))
      (node (ref "C76") (pin "2") (pinfunction "2_2") (pintype "passive"))
      (node (ref "C77") (pin "2") (pinfunction "2_2") (pintype "passive"))
      (node (ref "C78") (pin "2") (pinfunction "2_2") (pintype "passive"))
      (node (ref "C79") (pin "2") (pinfunction "2_2") (pintype "passive"))
      (node (ref "C80") (pin "2") (pinfunction "2_2") (pintype "passive"))
      (node (ref "D1") (pin "A") (pinfunction "A_A") (pintype "passive"))
      (node (ref "J1") (pin "P1") (pinfunction "P1_P1") (pintype "passive"))
      (node (ref "J1") (pin "P2") (pinfunction "P2_P2") (pintype "passive"))
      (node (ref "J14") (pin "1") (pinfunction "1_1") (pintype "passive"))
      (node (ref "J14") (pin "11") (pinfunction "11_11") (pintype "passive"))
      (node (ref "J14") (pin "13") (pinfunction "13_13") (pintype "passive"))
      (node (ref "J14") (pin "15") (pinfunction "15_15") (pintype "passive"))
      (node (ref "J14") (pin "17") (pinfunction "17_17") (pintype "passive"))
      (node (ref "J14") (pin "21") (pinfunction "21_21") (pintype "passive"))
      (node (ref "J14") (pin "22") (pinfunction "22_22") (pintype "passive"))
      (node (ref "J14") (pin "23") (pinfunction "23_23") (pintype "passive"))
      (node (ref "J14") (pin "24") (pinfunction "24_24") (pintype "passive"))
      (node (ref "J14") (pin "27") (pinfunction "27_27") (pintype "passive"))
      (node (ref "J14") (pin "3") (pinfunction "3_3") (pintype "passive"))
      (node (ref "J14") (pin "30") (pinfunction "30_30") (pintype "passive"))
      (node (ref "J14") (pin "33") (pinfunction "33_33") (pintype "passive"))
      (node (ref "J14") (pin "36") (pinfunction "36_36") (pintype "passive"))
      (node (ref "J14") (pin "39") (pinfunction "39_39") (pintype "passive"))
      (node (ref "J14") (pin "42") (pinfunction "42_42") (pintype "passive"))
      (node (ref "J14") (pin "6") (pinfunction "6_6") (pintype "passive"))
      (node (ref "J14") (pin "61") (pintype "passive"))
      (node (ref "J14") (pin "64") (pintype "passive"))
      (node (ref "J14") (pin "66") (pintype "passive"))
      (node (ref "J14") (pin "9") (pinfunction "9_9") (pintype "passive"))
      (node (ref "J14") (pin "M1") (pinfunction "M1_M1") (pintype "passive"))
      (node (ref "J14") (pin "M2") (pinfunction "M2_M2") (pintype "passive"))
      (node (ref "J2") (pin "5") (pinfunction "5_5") (pintype "passive"))
      (node (ref "J2") (pin "7") (pinfunction "7_7") (pintype "passive"))
      (node (ref "J2") (pin "M1") (pinfunction "M1_M1") (pintype "passive"))
      (node (ref "J2") (pin "M2") (pinfunction "M2_M2") (pintype "passive"))
      (node (ref "J3") (pin "M1") (pinfunction "M1_M1") (pintype "passive"))
      (node (ref "J3") (pin "M2") (pinfunction "M2_M2") (pintype "passive"))
      (node (ref "R10") (pin "1") (pinfunction "1_1") (pintype "passive"))
      (node (ref "R11") (pin "1") (pinfunction "1_1") (pintype "passive"))
      (node (ref "R329") (pin "2") (pinfunction "2_2") (pintype "passive"))
      (node (ref "R330") (pin "2") (pinfunction "2_2") (pintype "passive"))
      (node (ref "R7") (pin "2") (pinfunction "2_2") (pintype "passive"))
      (node (ref "SD1") (pin "10") (pinfunction "DL_10") (pintype "passive"))
      (node (ref "SD1") (pin "6") (pinfunction "VSS_6") (pintype "power_in"))
    )
    (net (code "69") (name "Net-(C46-Pad1)") (class "Default")
      (node (ref "C46") (pin "1") (pinfunction "1_1") (pintype "passive"))
      (node (ref "J14") (pin "2") (pinfunction "2_2") (pintype "passive"))
      (node (ref "R4") (pin "1") (pinfunction "1_1") (pintype "passive"))
      (node (ref "R5") (pin "2") (pinfunction "2_2") (pintype "passive"))
    )
    (net (code "70") (name "Net-(C52-Pad1)") (class "Default")
      (node (ref "C52") (pin "1") (pinfunction "1_1") (pintype "passive"))
      (node (ref "J1") (pin "8") (pinfunction "8_8") (pintype "passive"))
      (node (ref "R6") (pin "1") (pinfunction "1_1") (pintype "passive"))
    )
    (net (code "71") (name "Net-(C58-Pad1)") (class "Default")
      (node (ref "C58") (pin "1") (pinfunction "1_1") (pintype "passive"))
      (node (ref "J14") (pin "19") (pinfunction "19_19") (pintype "passive"))
      (node (ref "R10") (pin "2") (pinfunction "2_2") (pintype "passive"))
      (node (ref "R9") (pin "2") (pinfunction "2_2") (pintype "passive"))
    )
    (net (code "72") (name "Net-(C59-Pad1)") (class "Default")
      (node (ref "C59") (pin "1") (pinfunction "1_1") (pintype "passive"))
      (node (ref "J14") (pin "20") (pinfunction "20_20") (pintype "passive"))
      (node (ref "R11") (pin "2") (pinfunction "2_2") (pintype "passive"))
      (node (ref "R8") (pin "2") (pinfunction "2_2") (pintype "passive"))
    )
    (net (code "73") (name "Net-(C66-Pad1)") (class "Default")
      (node (ref "C66") (pin "1") (pinfunction "1_1") (pintype "passive"))
      (node (ref "FB30") (pin "2") (pinfunction "2_2") (pintype "passive"))
      (node (ref "J14") (pin "25") (pinfunction "25_25") (pintype "passive"))
      (node (ref "J14") (pin "26") (pinfunction "26_26") (pintype "passive"))
    )
    (net (code "74") (name "Net-(C421-Pad2)") (class "Default")
      (node (ref "C421") (pin "2") (pinfunction "2_2") (pintype "passive"))
      (node (ref "R330") (pin "1") (pinfunction "1_1") (pintype "passive"))
    )
    (net (code "75") (name "VCOM") (class "Default")
      (node (ref "C75") (pin "1") (pinfunction "1_1") (pintype "passive"))
      (node (ref "C76") (pin "1") (pinfunction "1_1") (pintype "passive"))
      (node (ref "J14") (pin "68") (pintype "passive"))
    )
    (net (code "76") (name "VDD") (class "Default")
      (node (ref "C64") (pin "1") (pinfunction "1_1") (pintype "passive"))
      (node (ref "C65") (pin "1") (pinfunction "1_1") (pintype "passive"))
      (node (ref "FB30") (pin "1") (pinfunction "1_1") (pintype "passive"))
    )
    (net (code "77") (name "VGH") (class "Default")
      (node (ref "C78") (pin "1") (pinfunction "1_1") (pintype "passive"))
      (node (ref "J14") (pin "65") (pintype "passive"))
    )
    (net (code "78") (name "VGL") (class "Default")
      (node (ref "C77") (pin "1") (pinfunction "1_1") (pintype "passive"))
      (node (ref "J14") (pin "67") (pintype "passive"))
    )
    (net (code "79") (name "unconnected-(SD1-SM-Pad11)") (class "Default")
      (node (ref "SD1") (pin "11") (pinfunction "SM_11") (pintype "passive+no_connect"))
    )
    (net (code "80") (name "unconnected-(SD1-SM-Pad12)") (class "Default")
      (node (ref "SD1") (pin "12") (pinfunction "SM_12") (pintype "passive+no_connect"))
    )
    (net (code "81") (name "unconnected-(SD1-SM-Pad13)") (class "Default")
      (node (ref "SD1") (pin "13") (pinfunction "SM_13") (pintype "passive+no_connect"))
    )
    (net (code "82") (name "unconnected-(SD1-SM-Pad14)") (class "Default")
      (node (ref "SD1") (pin "14") (pinfunction "SM_14") (pintype "passive+no_connect"))
    )
  )
)
